# CONNECTORS.net
KiCad netlist of a schematic drawn in Altium Designer
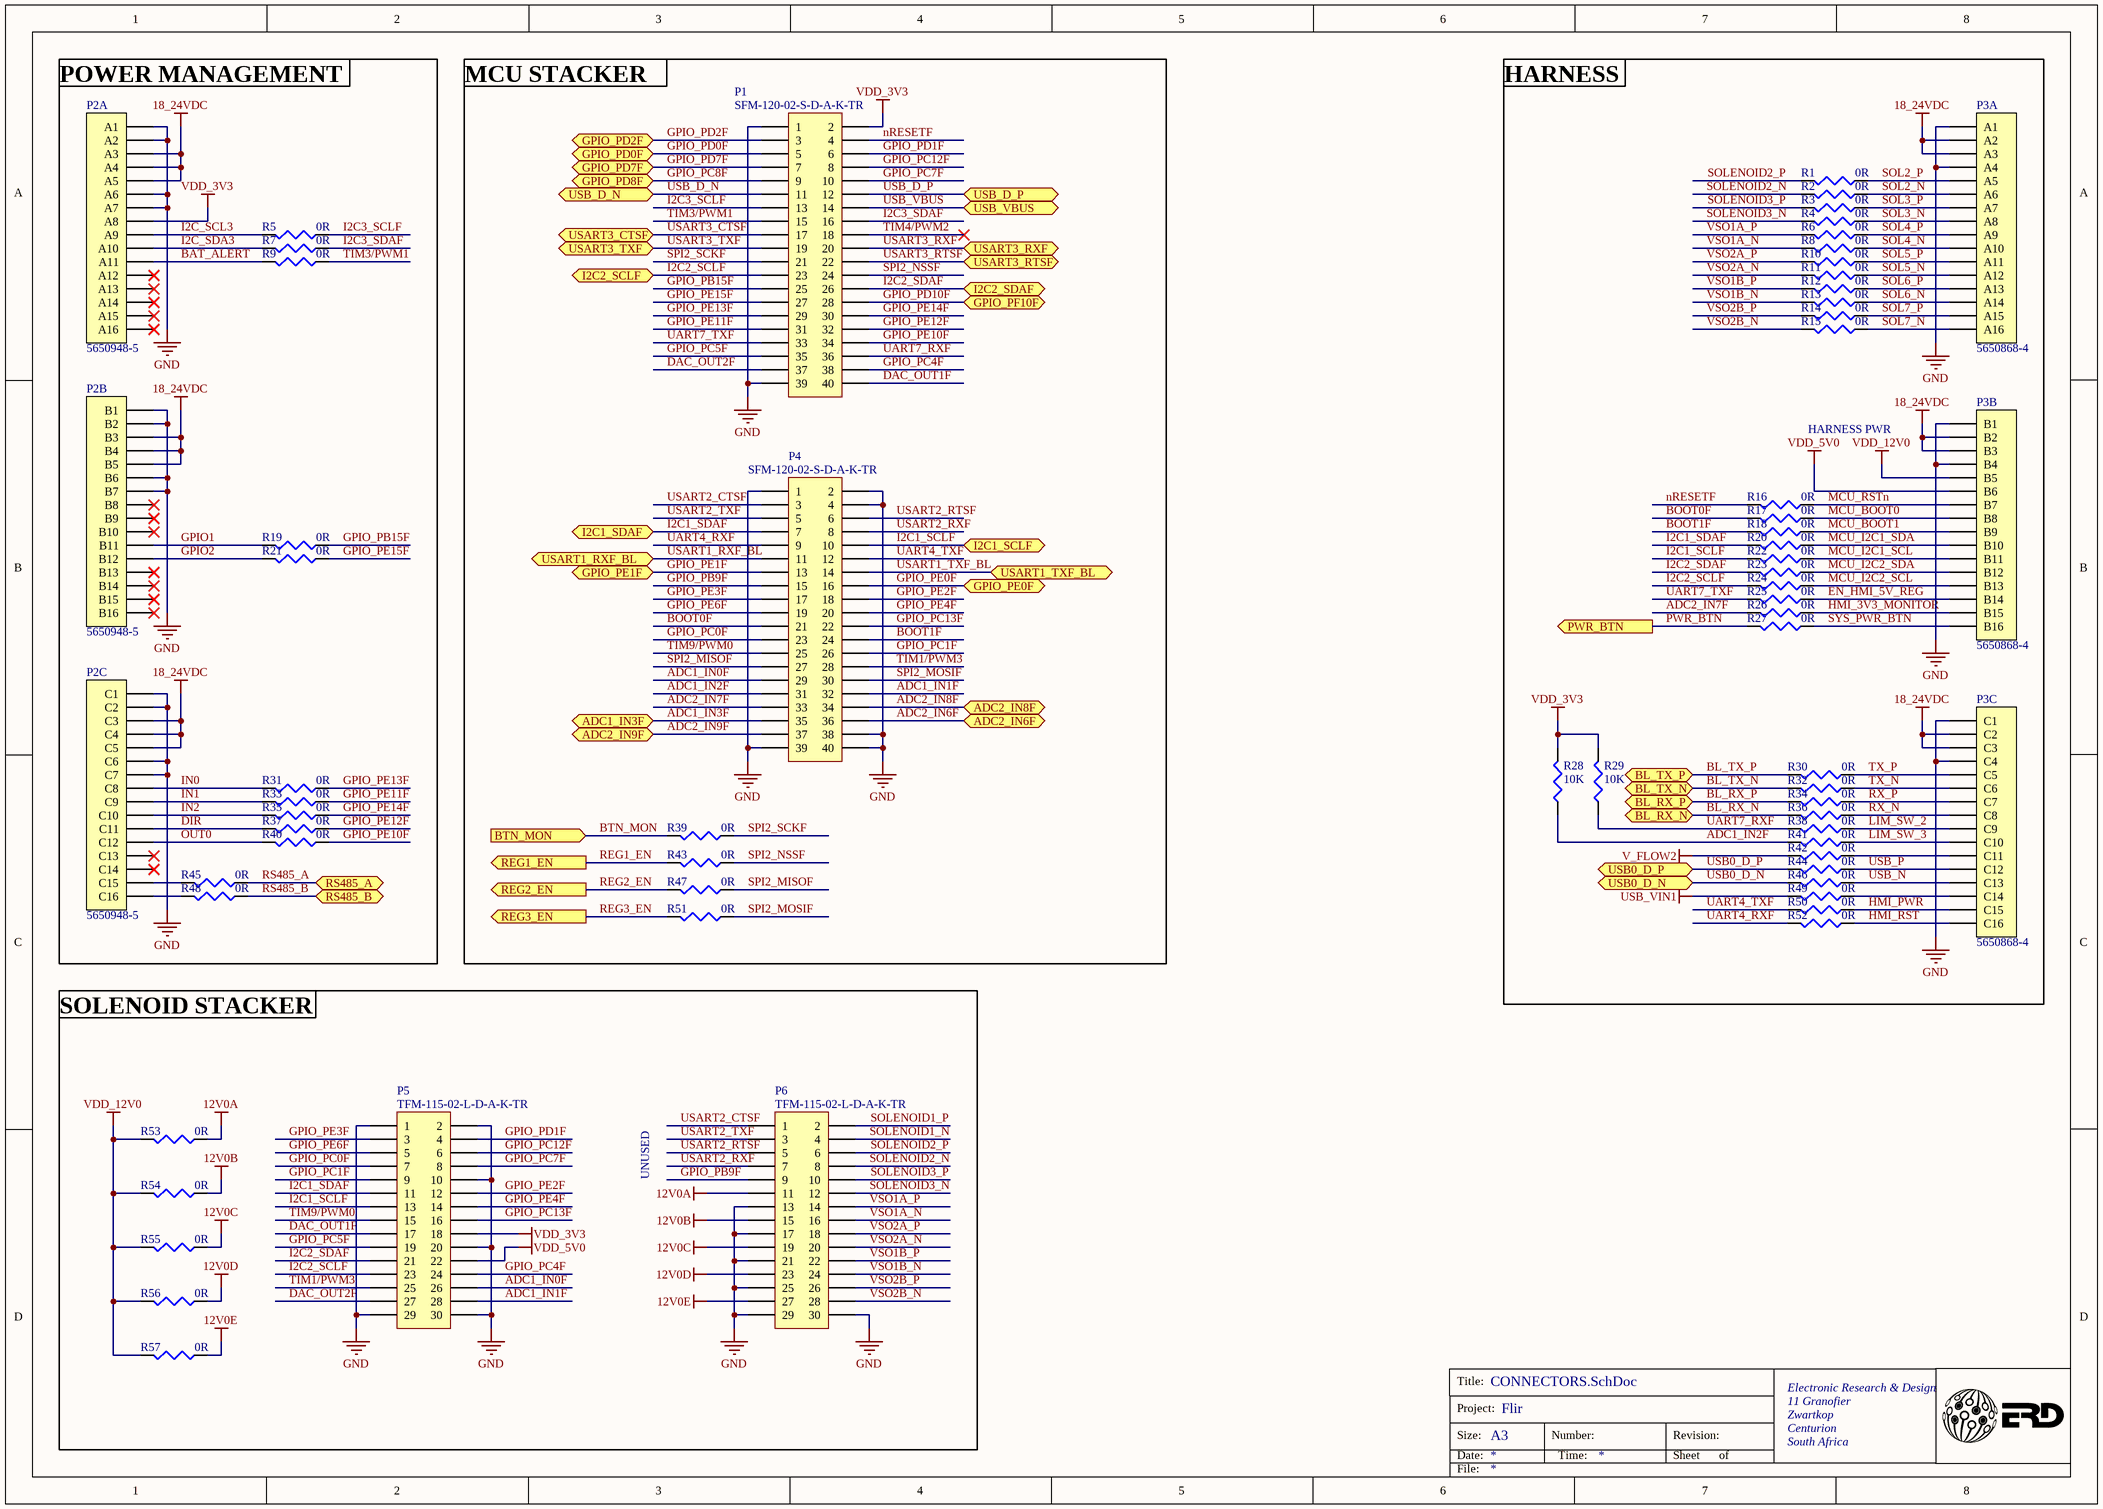
[diagram p0: CONNECTORS.SchDoc]

(export (version "E")
  (design (tool "Eeschema 10.0.6"))
  (components
    (comp (ref "P1")
      (value "SFM-120-02-S-D-A-K-TR")
      (footprint "ERD TiAm:SFM-120-02-S-D-A-K-TR")
      (description "Receptacle, 40 POS, 1.27mm PITCH, SMD")
      (libsource (lib "Miscellaneous Connectors") (part "Header 20X2"))
    )
    (comp (ref "P2")
      (value "5650948-5")
      (footprint "5650948-5_M_RA")
      (description "DIN-41612, C/2, 48-circuit, 3x16, 2.54mm pitch, RA, TH")
      (fields (field (name "MANUFACTURER") "TE Connectivity"))
      (libsource (lib "ERD TiAm") (part "DIN_41612_3x16"))
    )
    (comp (ref "P3")
      (value "5650868-4")
      (footprint "5650868-4_F_RA")
      (description "DIN-41612, R/2, 48-circuit, 3x16, 2.54mm pitch, RA, TH")
      (fields (field (name "MANUFACTURER") "TE Connectivity"))
      (libsource (lib "") (part "DIN_41612_3x16_1"))
    )
    (comp (ref "P4")
      (value "SFM-120-02-S-D-A-K-TR")
      (footprint "ERD TiAm:SFM-120-02-S-D-A-K-TR")
      (description "Receptacle, 40 POS, 1.27mm PITCH, SMD")
      (libsource (lib "Miscellaneous Connectors") (part "Header 20X2"))
    )
    (comp (ref "P5")
      (value "TFM-115-02-L-D-A-K-TR")
      (footprint "ERD TiAm:SFM-115-02-L-D-A-K-TR")
      (description "Header, 30 POS, 1.27mm PITCH, SMD")
      (libsource (lib "Miscellaneous Connectors") (part "Header 15X2"))
    )
    (comp (ref "P6")
      (value "TFM-115-02-L-D-A-K-TR")
      (footprint "ERD TiAm:SFM-115-02-L-D-A-K-TR")
      (description "Header, 30 POS, 1.27mm PITCH, SMD")
      (libsource (lib "Miscellaneous Connectors") (part "Header 15X2"))
    )
    (comp (ref "R1")
      (value "0R")
      (footprint "RC0402")
      (description "RES, 0 OHM, 1/16W, 1%, 0402")
      (fields (field (name "MANUFACTURER") "Yageo") (field (name "PARTNUMBER") "RC0402FR-070RL"))
      (libsource (lib "ERD TiAm") (part "RES_10K_1/16W_1%_0402"))
    )
    (comp (ref "R2")
      (value "0R")
      (footprint "RC0402")
      (description "RES, 0 OHM, 1/16W, 1%, 0402")
      (fields (field (name "MANUFACTURER") "Yageo") (field (name "PARTNUMBER") "RC0402FR-070RL"))
      (libsource (lib "ERD TiAm") (part "RES_10K_1/16W_1%_0402"))
    )
    (comp (ref "R3")
      (value "0R")
      (footprint "RC0402")
      (description "RES, 0 OHM, 1/16W, 1%, 0402")
      (fields (field (name "MANUFACTURER") "Yageo") (field (name "PARTNUMBER") "RC0402FR-070RL"))
      (libsource (lib "ERD TiAm") (part "RES_10K_1/16W_1%_0402"))
    )
    (comp (ref "R4")
      (value "0R")
      (footprint "RC0402")
      (description "RES, 0 OHM, 1/16W, 1%, 0402")
      (fields (field (name "MANUFACTURER") "Yageo") (field (name "PARTNUMBER") "RC0402FR-070RL"))
      (libsource (lib "ERD TiAm") (part "RES_10K_1/16W_1%_0402"))
    )
    (comp (ref "R5")
      (value "0R")
      (footprint "RC0402")
      (description "RES, 0 OHM, 1/16W, 1%, 0402")
      (fields (field (name "MANUFACTURER") "Yageo") (field (name "PARTNUMBER") "RC0402FR-070RL"))
      (libsource (lib "ERD TiAm") (part "RES_10K_1/16W_1%_0402"))
    )
    (comp (ref "R6")
      (value "0R")
      (footprint "RC0402")
      (description "RES, 0 OHM, 1/16W, 1%, 0402")
      (fields (field (name "MANUFACTURER") "Yageo") (field (name "PARTNUMBER") "RC0402FR-070RL"))
      (libsource (lib "ERD TiAm") (part "RES_10K_1/16W_1%_0402"))
    )
    (comp (ref "R7")
      (value "0R")
      (footprint "RC0402")
      (description "RES, 0 OHM, 1/16W, 1%, 0402")
      (fields (field (name "MANUFACTURER") "Yageo") (field (name "PARTNUMBER") "RC0402FR-070RL"))
      (libsource (lib "ERD TiAm") (part "RES_10K_1/16W_1%_0402"))
    )
    (comp (ref "R8")
      (value "0R")
      (footprint "RC0402")
      (description "RES, 0 OHM, 1/16W, 1%, 0402")
      (fields (field (name "MANUFACTURER") "Yageo") (field (name "PARTNUMBER") "RC0402FR-070RL"))
      (libsource (lib "ERD TiAm") (part "RES_10K_1/16W_1%_0402"))
    )
    (comp (ref "R9")
      (value "0R")
      (footprint "RC0402")
      (description "RES, 0 OHM, 1/16W, 1%, 0402")
      (fields (field (name "MANUFACTURER") "Yageo") (field (name "PARTNUMBER") "RC0402FR-070RL"))
      (libsource (lib "ERD TiAm") (part "RES_10K_1/16W_1%_0402"))
    )
    (comp (ref "R10")
      (value "0R")
      (footprint "RC0402")
      (description "RES, 0 OHM, 1/16W, 1%, 0402")
      (fields (field (name "MANUFACTURER") "Yageo") (field (name "PARTNUMBER") "RC0402FR-070RL"))
      (libsource (lib "ERD TiAm") (part "RES_10K_1/16W_1%_0402"))
    )
    (comp (ref "R11")
      (value "0R")
      (footprint "RC0402")
      (description "RES, 0 OHM, 1/16W, 1%, 0402")
      (fields (field (name "MANUFACTURER") "Yageo") (field (name "PARTNUMBER") "RC0402FR-070RL"))
      (libsource (lib "ERD TiAm") (part "RES_10K_1/16W_1%_0402"))
    )
    (comp (ref "R12")
      (value "0R")
      (footprint "RC0402")
      (description "RES, 0 OHM, 1/16W, 1%, 0402")
      (fields (field (name "MANUFACTURER") "Yageo") (field (name "PARTNUMBER") "RC0402FR-070RL"))
      (libsource (lib "ERD TiAm") (part "RES_10K_1/16W_1%_0402"))
    )
    (comp (ref "R13")
      (value "0R")
      (footprint "RC0402")
      (description "RES, 0 OHM, 1/16W, 1%, 0402")
      (fields (field (name "MANUFACTURER") "Yageo") (field (name "PARTNUMBER") "RC0402FR-070RL"))
      (libsource (lib "ERD TiAm") (part "RES_10K_1/16W_1%_0402"))
    )
    (comp (ref "R14")
      (value "0R")
      (footprint "RC0402")
      (description "RES, 0 OHM, 1/16W, 1%, 0402")
      (fields (field (name "MANUFACTURER") "Yageo") (field (name "PARTNUMBER") "RC0402FR-070RL"))
      (libsource (lib "ERD TiAm") (part "RES_10K_1/16W_1%_0402"))
    )
    (comp (ref "R15")
      (value "0R")
      (footprint "RC0402")
      (description "RES, 0 OHM, 1/16W, 1%, 0402")
      (fields (field (name "MANUFACTURER") "Yageo") (field (name "PARTNUMBER") "RC0402FR-070RL"))
      (libsource (lib "ERD TiAm") (part "RES_10K_1/16W_1%_0402"))
    )
    (comp (ref "R16")
      (value "0R")
      (footprint "RC0402")
      (description "RES, 0 OHM, 1/16W, 1%, 0402")
      (fields (field (name "MANUFACTURER") "Yageo") (field (name "PARTNUMBER") "RC0402FR-070RL"))
      (libsource (lib "ERD TiAm") (part "RES_10K_1/16W_1%_0402"))
    )
    (comp (ref "R17")
      (value "0R")
      (footprint "RC0402")
      (description "RES, 0 OHM, 1/16W, 1%, 0402")
      (fields (field (name "MANUFACTURER") "Yageo") (field (name "PARTNUMBER") "RC0402FR-070RL"))
      (libsource (lib "ERD TiAm") (part "RES_10K_1/16W_1%_0402"))
    )
    (comp (ref "R18")
      (value "0R")
      (footprint "RC0402")
      (description "RES, 0 OHM, 1/16W, 1%, 0402")
      (fields (field (name "MANUFACTURER") "Yageo") (field (name "PARTNUMBER") "RC0402FR-070RL"))
      (libsource (lib "ERD TiAm") (part "RES_10K_1/16W_1%_0402"))
    )
    (comp (ref "R19")
      (value "0R")
      (footprint "RC0402")
      (description "RES, 0 OHM, 1/16W, 1%, 0402")
      (fields (field (name "MANUFACTURER") "Yageo") (field (name "PARTNUMBER") "RC0402FR-070RL"))
      (libsource (lib "ERD TiAm") (part "RES_10K_1/16W_1%_0402"))
    )
    (comp (ref "R20")
      (value "0R")
      (footprint "RC0402")
      (description "RES, 0 OHM, 1/16W, 1%, 0402")
      (fields (field (name "MANUFACTURER") "Yageo") (field (name "PARTNUMBER") "RC0402FR-070RL"))
      (libsource (lib "ERD TiAm") (part "RES_10K_1/16W_1%_0402"))
    )
    (comp (ref "R21")
      (value "0R")
      (footprint "RC0402")
      (description "RES, 0 OHM, 1/16W, 1%, 0402")
      (fields (field (name "MANUFACTURER") "Yageo") (field (name "PARTNUMBER") "RC0402FR-070RL"))
      (libsource (lib "ERD TiAm") (part "RES_10K_1/16W_1%_0402"))
    )
    (comp (ref "R22")
      (value "0R")
      (footprint "RC0402")
      (description "RES, 0 OHM, 1/16W, 1%, 0402")
      (fields (field (name "MANUFACTURER") "Yageo") (field (name "PARTNUMBER") "RC0402FR-070RL"))
      (libsource (lib "ERD TiAm") (part "RES_10K_1/16W_1%_0402"))
    )
    (comp (ref "R23")
      (value "0R")
      (footprint "RC0402")
      (description "RES, 0 OHM, 1/16W, 1%, 0402")
      (fields (field (name "MANUFACTURER") "Yageo") (field (name "PARTNUMBER") "RC0402FR-070RL"))
      (libsource (lib "ERD TiAm") (part "RES_10K_1/16W_1%_0402"))
    )
    (comp (ref "R24")
      (value "0R")
      (footprint "RC0402")
      (description "RES, 0 OHM, 1/16W, 1%, 0402")
      (fields (field (name "MANUFACTURER") "Yageo") (field (name "PARTNUMBER") "RC0402FR-070RL"))
      (libsource (lib "ERD TiAm") (part "RES_10K_1/16W_1%_0402"))
    )
    (comp (ref "R25")
      (value "0R")
      (footprint "RC0402")
      (description "RES, 0 OHM, 1/16W, 1%, 0402")
      (fields (field (name "MANUFACTURER") "Yageo") (field (name "PARTNUMBER") "RC0402FR-070RL"))
      (libsource (lib "ERD TiAm") (part "RES_10K_1/16W_1%_0402"))
    )
    (comp (ref "R26")
      (value "0R")
      (footprint "RC0402")
      (description "RES, 0 OHM, 1/16W, 1%, 0402")
      (fields (field (name "MANUFACTURER") "Yageo") (field (name "PARTNUMBER") "RC0402FR-070RL"))
      (libsource (lib "ERD TiAm") (part "RES_10K_1/16W_1%_0402"))
    )
    (comp (ref "R27")
      (value "0R")
      (footprint "RC0402")
      (description "RES, 0 OHM, 1/16W, 1%, 0402")
      (fields (field (name "MANUFACTURER") "Yageo") (field (name "PARTNUMBER") "RC0402FR-070RL"))
      (libsource (lib "ERD TiAm") (part "RES_10K_1/16W_1%_0402"))
    )
    (comp (ref "R28")
      (value "10K")
      (footprint "RC0402")
      (description "RES, 10K OHM, 1/16W, 1%, 0402")
      (fields (field (name "MANUFACTURER") "Yageo") (field (name "PART NUMBER") "RC0402FR-0710KL"))
      (libsource (lib "ERD TiAm") (part "RES_10K_1/16W_1%_0402"))
    )
    (comp (ref "R29")
      (value "10K")
      (footprint "RC0402")
      (description "RES, 10K OHM, 1/16W, 1%, 0402")
      (fields (field (name "MANUFACTURER") "Yageo") (field (name "PART NUMBER") "RC0402FR-0710KL"))
      (libsource (lib "ERD TiAm") (part "RES_10K_1/16W_1%_0402"))
    )
    (comp (ref "R30")
      (value "0R")
      (footprint "RC0402")
      (description "RES, 0 OHM, 1/16W, 1%, 0402")
      (fields (field (name "MANUFACTURER") "Yageo") (field (name "PARTNUMBER") "RC0402FR-070RL"))
      (libsource (lib "ERD TiAm") (part "RES_10K_1/16W_1%_0402"))
    )
    (comp (ref "R31")
      (value "0R")
      (footprint "RC0402")
      (description "RES, 0 OHM, 1/16W, 1%, 0402")
      (fields (field (name "MANUFACTURER") "Yageo") (field (name "PARTNUMBER") "RC0402FR-070RL"))
      (libsource (lib "ERD TiAm") (part "RES_10K_1/16W_1%_0402"))
    )
    (comp (ref "R32")
      (value "0R")
      (footprint "RC0402")
      (description "RES, 0 OHM, 1/16W, 1%, 0402")
      (fields (field (name "MANUFACTURER") "Yageo") (field (name "PARTNUMBER") "RC0402FR-070RL"))
      (libsource (lib "ERD TiAm") (part "RES_10K_1/16W_1%_0402"))
    )
    (comp (ref "R33")
      (value "0R")
      (footprint "RC0402")
      (description "RES, 0 OHM, 1/16W, 1%, 0402")
      (fields (field (name "MANUFACTURER") "Yageo") (field (name "PARTNUMBER") "RC0402FR-070RL"))
      (libsource (lib "ERD TiAm") (part "RES_10K_1/16W_1%_0402"))
    )
    (comp (ref "R34")
      (value "0R")
      (footprint "RC0402")
      (description "RES, 0 OHM, 1/16W, 1%, 0402")
      (fields (field (name "MANUFACTURER") "Yageo") (field (name "PARTNUMBER") "RC0402FR-070RL"))
      (libsource (lib "ERD TiAm") (part "RES_10K_1/16W_1%_0402"))
    )
    (comp (ref "R35")
      (value "0R")
      (footprint "RC0402")
      (description "RES, 0 OHM, 1/16W, 1%, 0402")
      (fields (field (name "MANUFACTURER") "Yageo") (field (name "PARTNUMBER") "RC0402FR-070RL"))
      (libsource (lib "ERD TiAm") (part "RES_10K_1/16W_1%_0402"))
    )
    (comp (ref "R36")
      (value "0R")
      (footprint "RC0402")
      (description "RES, 0 OHM, 1/16W, 1%, 0402")
      (fields (field (name "MANUFACTURER") "Yageo") (field (name "PARTNUMBER") "RC0402FR-070RL"))
      (libsource (lib "ERD TiAm") (part "RES_10K_1/16W_1%_0402"))
    )
    (comp (ref "R37")
      (value "0R")
      (footprint "RC0402")
      (description "RES, 0 OHM, 1/16W, 1%, 0402")
      (fields (field (name "MANUFACTURER") "Yageo") (field (name "PARTNUMBER") "RC0402FR-070RL"))
      (libsource (lib "ERD TiAm") (part "RES_10K_1/16W_1%_0402"))
    )
    (comp (ref "R38")
      (value "0R")
      (footprint "RC0402")
      (description "RES, 0 OHM, 1/16W, 1%, 0402")
      (fields (field (name "MANUFACTURER") "Yageo") (field (name "PARTNUMBER") "RC0402FR-070RL"))
      (libsource (lib "ERD TiAm") (part "RES_10K_1/16W_1%_0402"))
    )
    (comp (ref "R39")
      (value "0R")
      (footprint "RC0402")
      (description "RES, 0 OHM, 1/16W, 1%, 0402")
      (fields (field (name "MANUFACTURER") "Yageo") (field (name "PARTNUMBER") "RC0402FR-070RL"))
      (libsource (lib "ERD TiAm") (part "RES_10K_1/16W_1%_0402"))
    )
    (comp (ref "R40")
      (value "0R")
      (footprint "RC0402")
      (description "RES, 0 OHM, 1/16W, 1%, 0402")
      (fields (field (name "MANUFACTURER") "Yageo") (field (name "PARTNUMBER") "RC0402FR-070RL"))
      (libsource (lib "ERD TiAm") (part "RES_10K_1/16W_1%_0402"))
    )
    (comp (ref "R41")
      (value "0R")
      (footprint "RC0402")
      (description "RES, 0 OHM, 1/16W, 1%, 0402")
      (fields (field (name "MANUFACTURER") "Yageo") (field (name "PARTNUMBER") "RC0402FR-070RL"))
      (libsource (lib "ERD TiAm") (part "RES_10K_1/16W_1%_0402"))
    )
    (comp (ref "R42")
      (value "0R")
      (footprint "RC0402")
      (description "RES, 0 OHM, 1/16W, 1%, 0402")
      (fields (field (name "MANUFACTURER") "Yageo") (field (name "PARTNUMBER") "RC0402FR-070RL"))
      (libsource (lib "ERD TiAm") (part "RES_10K_1/16W_1%_0402"))
    )
    (comp (ref "R43")
      (value "0R")
      (footprint "RC0402")
      (description "RES, 0 OHM, 1/16W, 1%, 0402")
      (fields (field (name "MANUFACTURER") "Yageo") (field (name "PARTNUMBER") "RC0402FR-070RL"))
      (libsource (lib "ERD TiAm") (part "RES_10K_1/16W_1%_0402"))
    )
    (comp (ref "R44")
      (value "0R")
      (footprint "RC0402")
      (description "RES, 0 OHM, 1/16W, 1%, 0402")
      (fields (field (name "MANUFACTURER") "Yageo") (field (name "PARTNUMBER") "RC0402FR-070RL"))
      (libsource (lib "ERD TiAm") (part "RES_10K_1/16W_1%_0402"))
    )
    (comp (ref "R45")
      (value "0R")
      (footprint "RC0402")
      (description "RES, 0 OHM, 1/16W, 1%, 0402")
      (fields (field (name "MANUFACTURER") "Yageo") (field (name "PARTNUMBER") "RC0402FR-070RL"))
      (libsource (lib "ERD TiAm") (part "RES_10K_1/16W_1%_0402"))
    )
    (comp (ref "R46")
      (value "0R")
      (footprint "RC0402")
      (description "RES, 0 OHM, 1/16W, 1%, 0402")
      (fields (field (name "MANUFACTURER") "Yageo") (field (name "PARTNUMBER") "RC0402FR-070RL"))
      (libsource (lib "ERD TiAm") (part "RES_10K_1/16W_1%_0402"))
    )
    (comp (ref "R47")
      (value "0R")
      (footprint "RC0402")
      (description "RES, 0 OHM, 1/16W, 1%, 0402")
      (fields (field (name "MANUFACTURER") "Yageo") (field (name "PARTNUMBER") "RC0402FR-070RL"))
      (libsource (lib "ERD TiAm") (part "RES_10K_1/16W_1%_0402"))
    )
    (comp (ref "R48")
      (value "0R")
      (footprint "RC0402")
      (description "RES, 0 OHM, 1/16W, 1%, 0402")
      (fields (field (name "MANUFACTURER") "Yageo") (field (name "PARTNUMBER") "RC0402FR-070RL"))
      (libsource (lib "ERD TiAm") (part "RES_10K_1/16W_1%_0402"))
    )
    (comp (ref "R49")
      (value "0R")
      (footprint "RC0402")
      (description "RES, 0 OHM, 1/16W, 1%, 0402")
      (fields (field (name "MANUFACTURER") "Yageo") (field (name "PARTNUMBER") "RC0402FR-070RL"))
      (libsource (lib "ERD TiAm") (part "RES_10K_1/16W_1%_0402"))
    )
    (comp (ref "R50")
      (value "0R")
      (footprint "RC0402")
      (description "RES, 0 OHM, 1/16W, 1%, 0402")
      (fields (field (name "MANUFACTURER") "Yageo") (field (name "PARTNUMBER") "RC0402FR-070RL"))
      (libsource (lib "ERD TiAm") (part "RES_10K_1/16W_1%_0402"))
    )
    (comp (ref "R51")
      (value "0R")
      (footprint "RC0402")
      (description "RES, 0 OHM, 1/16W, 1%, 0402")
      (fields (field (name "MANUFACTURER") "Yageo") (field (name "PARTNUMBER") "RC0402FR-070RL"))
      (libsource (lib "ERD TiAm") (part "RES_10K_1/16W_1%_0402"))
    )
    (comp (ref "R52")
      (value "0R")
      (footprint "RC0402")
      (description "RES, 0 OHM, 1/16W, 1%, 0402")
      (fields (field (name "MANUFACTURER") "Yageo") (field (name "PARTNUMBER") "RC0402FR-070RL"))
      (libsource (lib "ERD TiAm") (part "RES_10K_1/16W_1%_0402"))
    )
    (comp (ref "R53")
      (value "0R")
      (footprint "RC0603")
      (description "RES, 0 OHM, 1/10W, 50mOhm (5%), 0603")
      (fields (field (name "MANUFACTURER") "Yageo") (field (name "PARTNUMBER") "RC0603JR-070RP"))
      (libsource (lib "ERD TiAm") (part "RES_10K_1/16W_1%_0402"))
    )
    (comp (ref "R54")
      (value "0R")
      (footprint "RC0603")
      (description "RES, 0 OHM, 1/10W, 50mOhm (5%), 0603")
      (fields (field (name "MANUFACTURER") "Yageo") (field (name "PARTNUMBER") "RC0603JR-070RP"))
      (libsource (lib "ERD TiAm") (part "RES_10K_1/16W_1%_0402"))
    )
    (comp (ref "R55")
      (value "0R")
      (footprint "RC0603")
      (description "RES, 0 OHM, 1/10W, 50mOhm (5%), 0603")
      (fields (field (name "MANUFACTURER") "Yageo") (field (name "PARTNUMBER") "RC0603JR-070RP"))
      (libsource (lib "ERD TiAm") (part "RES_10K_1/16W_1%_0402"))
    )
    (comp (ref "R56")
      (value "0R")
      (footprint "RC0603")
      (description "RES, 0 OHM, 1/10W, 50mOhm (5%), 0603")
      (fields (field (name "MANUFACTURER") "Yageo") (field (name "PARTNUMBER") "RC0603JR-070RP"))
      (libsource (lib "ERD TiAm") (part "RES_10K_1/16W_1%_0402"))
    )
    (comp (ref "R57")
      (value "0R")
      (footprint "RC0603")
      (description "RES, 0 OHM, 1/10W, 50mOhm (5%), 0603")
      (fields (field (name "MANUFACTURER") "Yageo") (field (name "PARTNUMBER") "RC0603JR-070RP"))
      (libsource (lib "ERD TiAm") (part "RES_10K_1/16W_1%_0402"))
    )
  )
  (nets
    (net (code "1") (name "/ADC1_IN0F") (class "Default")
      (node (ref "P4") (pin "29") (pinfunction "29_29") (pintype "passive"))
      (node (ref "P5") (pin "26") (pinfunction "26_26") (pintype "passive"))
    )
    (net (code "2") (name "/ADC1_IN1F") (class "Default")
      (node (ref "P4") (pin "32") (pinfunction "32_32") (pintype "passive"))
      (node (ref "P5") (pin "28") (pinfunction "28_28") (pintype "passive"))
    )
    (net (code "3") (name "/ADC1_IN2F") (class "Default")
      (node (ref "P4") (pin "31") (pinfunction "31_31") (pintype "passive"))
      (node (ref "R28") (pin "1") (pinfunction "1_1") (pintype "passive"))
      (node (ref "R41") (pin "2") (pinfunction "2_2") (pintype "passive"))
    )
    (net (code "4") (name "/ADC1_IN3F") (class "Default")
      (node (ref "P4") (pin "35") (pinfunction "35_35") (pintype "passive"))
    )
    (net (code "5") (name "/ADC2_IN6F") (class "Default")
      (node (ref "P4") (pin "36") (pinfunction "36_36") (pintype "passive"))
    )
    (net (code "6") (name "/ADC2_IN7F") (class "Default")
      (node (ref "P4") (pin "33") (pinfunction "33_33") (pintype "passive"))
      (node (ref "R26") (pin "2") (pinfunction "2_2") (pintype "passive"))
    )
    (net (code "7") (name "/ADC2_IN8F") (class "Default")
      (node (ref "P4") (pin "34") (pinfunction "34_34") (pintype "passive"))
    )
    (net (code "8") (name "/ADC2_IN9F") (class "Default")
      (node (ref "P4") (pin "37") (pinfunction "37_37") (pintype "passive"))
    )
    (net (code "9") (name "/BAT_ALERT") (class "Default")
      (node (ref "P2") (pin "11") (pinfunction "A11_11") (pintype "passive"))
      (node (ref "R9") (pin "2") (pinfunction "2_2") (pintype "passive"))
    )
    (net (code "10") (name "/BL_RX_N") (class "Default")
      (node (ref "R36") (pin "2") (pinfunction "2_2") (pintype "passive"))
    )
    (net (code "11") (name "/BL_RX_P") (class "Default")
      (node (ref "R34") (pin "2") (pinfunction "2_2") (pintype "passive"))
    )
    (net (code "12") (name "/BL_TX_N") (class "Default")
      (node (ref "R32") (pin "2") (pinfunction "2_2") (pintype "passive"))
    )
    (net (code "13") (name "/BL_TX_P") (class "Default")
      (node (ref "R30") (pin "2") (pinfunction "2_2") (pintype "passive"))
    )
    (net (code "14") (name "/BOOT0F") (class "Default")
      (node (ref "P4") (pin "21") (pinfunction "21_21") (pintype "passive"))
      (node (ref "R17") (pin "2") (pinfunction "2_2") (pintype "passive"))
    )
    (net (code "15") (name "/BOOT1F") (class "Default")
      (node (ref "P4") (pin "24") (pinfunction "24_24") (pintype "passive"))
      (node (ref "R18") (pin "2") (pinfunction "2_2") (pintype "passive"))
    )
    (net (code "16") (name "/BTN_MON") (class "Default")
      (node (ref "R39") (pin "2") (pinfunction "2_2") (pintype "passive"))
    )
    (net (code "17") (name "/DAC_OUT1F") (class "Default")
      (node (ref "P1") (pin "40") (pinfunction "40_40") (pintype "passive"))
      (node (ref "P5") (pin "17") (pinfunction "17_17") (pintype "passive"))
    )
    (net (code "18") (name "/DAC_OUT2F") (class "Default")
      (node (ref "P1") (pin "37") (pinfunction "37_37") (pintype "passive"))
      (node (ref "P5") (pin "27") (pinfunction "27_27") (pintype "passive"))
    )
    (net (code "19") (name "/DIR") (class "Default")
      (node (ref "P2") (pin "43") (pinfunction "C11_43") (pintype "passive"))
      (node (ref "R37") (pin "2") (pinfunction "2_2") (pintype "passive"))
    )
    (net (code "20") (name "/EN_HMI_5V_REG") (class "Default")
      (node (ref "P3") (pin "30") (pinfunction "B14_30") (pintype "passive"))
      (node (ref "R25") (pin "1") (pinfunction "1_1") (pintype "passive"))
    )
    (net (code "21") (name "/GPIO1") (class "Default")
      (node (ref "P2") (pin "27") (pinfunction "B11_27") (pintype "passive"))
      (node (ref "R19") (pin "2") (pinfunction "2_2") (pintype "passive"))
    )
    (net (code "22") (name "/GPIO2") (class "Default")
      (node (ref "P2") (pin "28") (pinfunction "B12_28") (pintype "passive"))
      (node (ref "R21") (pin "2") (pinfunction "2_2") (pintype "passive"))
    )
    (net (code "23") (name "/GPIO_PB9F") (class "Default")
      (node (ref "P4") (pin "15") (pinfunction "15_15") (pintype "passive"))
      (node (ref "P6") (pin "9") (pinfunction "9_9") (pintype "passive"))
    )
    (net (code "24") (name "/GPIO_PB15F") (class "Default")
      (node (ref "P1") (pin "25") (pinfunction "25_25") (pintype "passive"))
      (node (ref "R19") (pin "1") (pinfunction "1_1") (pintype "passive"))
    )
    (net (code "25") (name "/GPIO_PC0F") (class "Default")
      (node (ref "P4") (pin "23") (pinfunction "23_23") (pintype "passive"))
      (node (ref "P5") (pin "7") (pinfunction "7_7") (pintype "passive"))
    )
    (net (code "26") (name "/GPIO_PC1F") (class "Default")
      (node (ref "P4") (pin "26") (pinfunction "26_26") (pintype "passive"))
      (node (ref "P5") (pin "9") (pinfunction "9_9") (pintype "passive"))
    )
    (net (code "27") (name "/GPIO_PC4F") (class "Default")
      (node (ref "P1") (pin "38") (pinfunction "38_38") (pintype "passive"))
      (node (ref "P5") (pin "24") (pinfunction "24_24") (pintype "passive"))
    )
    (net (code "28") (name "/GPIO_PC5F") (class "Default")
      (node (ref "P1") (pin "35") (pinfunction "35_35") (pintype "passive"))
      (node (ref "P5") (pin "19") (pinfunction "19_19") (pintype "passive"))
    )
    (net (code "29") (name "/GPIO_PC7F") (class "Default")
      (node (ref "P1") (pin "10") (pinfunction "10_10") (pintype "passive"))
      (node (ref "P5") (pin "8") (pinfunction "8_8") (pintype "passive"))
    )
    (net (code "30") (name "/GPIO_PC8F") (class "Default")
      (node (ref "P1") (pin "9") (pinfunction "9_9") (pintype "passive"))
    )
    (net (code "31") (name "/GPIO_PC12F") (class "Default")
      (node (ref "P1") (pin "8") (pinfunction "8_8") (pintype "passive"))
      (node (ref "P5") (pin "6") (pinfunction "6_6") (pintype "passive"))
    )
    (net (code "32") (name "/GPIO_PC13F") (class "Default")
      (node (ref "P4") (pin "22") (pinfunction "22_22") (pintype "passive"))
      (node (ref "P5") (pin "16") (pinfunction "16_16") (pintype "passive"))
    )
    (net (code "33") (name "/GPIO_PD0F") (class "Default")
      (node (ref "P1") (pin "5") (pinfunction "5_5") (pintype "passive"))
    )
    (net (code "34") (name "/GPIO_PD1F") (class "Default")
      (node (ref "P1") (pin "6") (pinfunction "6_6") (pintype "passive"))
      (node (ref "P5") (pin "4") (pinfunction "4_4") (pintype "passive"))
    )
    (net (code "35") (name "/GPIO_PD2F") (class "Default")
      (node (ref "P1") (pin "3") (pinfunction "3_3") (pintype "passive"))
    )
    (net (code "36") (name "/GPIO_PD7F") (class "Default")
      (node (ref "P1") (pin "7") (pinfunction "7_7") (pintype "passive"))
    )
    (net (code "37") (name "/GPIO_PD10F") (class "Default")
      (node (ref "P1") (pin "28") (pinfunction "28_28") (pintype "passive"))
    )
    (net (code "38") (name "/GPIO_PE0F") (class "Default")
      (node (ref "P4") (pin "16") (pinfunction "16_16") (pintype "passive"))
    )
    (net (code "39") (name "/GPIO_PE1F") (class "Default")
      (node (ref "P4") (pin "13") (pinfunction "13_13") (pintype "passive"))
    )
    (net (code "40") (name "/GPIO_PE2F") (class "Default")
      (node (ref "P4") (pin "18") (pinfunction "18_18") (pintype "passive"))
      (node (ref "P5") (pin "12") (pinfunction "12_12") (pintype "passive"))
    )
    (net (code "41") (name "/GPIO_PE3F") (class "Default")
      (node (ref "P4") (pin "17") (pinfunction "17_17") (pintype "passive"))
      (node (ref "P5") (pin "3") (pinfunction "3_3") (pintype "passive"))
    )
    (net (code "42") (name "/GPIO_PE4F") (class "Default")
      (node (ref "P4") (pin "20") (pinfunction "20_20") (pintype "passive"))
      (node (ref "P5") (pin "14") (pinfunction "14_14") (pintype "passive"))
    )
    (net (code "43") (name "/GPIO_PE6F") (class "Default")
      (node (ref "P4") (pin "19") (pinfunction "19_19") (pintype "passive"))
      (node (ref "P5") (pin "5") (pinfunction "5_5") (pintype "passive"))
    )
    (net (code "44") (name "/GPIO_PE10F") (class "Default")
      (node (ref "P1") (pin "34") (pinfunction "34_34") (pintype "passive"))
      (node (ref "R40") (pin "1") (pinfunction "1_1") (pintype "passive"))
    )
    (net (code "45") (name "/GPIO_PE11F") (class "Default")
      (node (ref "P1") (pin "31") (pinfunction "31_31") (pintype "passive"))
      (node (ref "R33") (pin "1") (pinfunction "1_1") (pintype "passive"))
    )
    (net (code "46") (name "/GPIO_PE12F") (class "Default")
      (node (ref "P1") (pin "32") (pinfunction "32_32") (pintype "passive"))
      (node (ref "R37") (pin "1") (pinfunction "1_1") (pintype "passive"))
    )
    (net (code "47") (name "/GPIO_PE13F") (class "Default")
      (node (ref "P1") (pin "29") (pinfunction "29_29") (pintype "passive"))
      (node (ref "R31") (pin "1") (pinfunction "1_1") (pintype "passive"))
    )
    (net (code "48") (name "/GPIO_PE14F") (class "Default")
      (node (ref "P1") (pin "30") (pinfunction "30_30") (pintype "passive"))
      (node (ref "R35") (pin "1") (pinfunction "1_1") (pintype "passive"))
    )
    (net (code "49") (name "/GPIO_PE15F") (class "Default")
      (node (ref "P1") (pin "27") (pinfunction "27_27") (pintype "passive"))
      (node (ref "R21") (pin "1") (pinfunction "1_1") (pintype "passive"))
    )
    (net (code "50") (name "/HMI_3V3_MONITOR") (class "Default")
      (node (ref "P3") (pin "31") (pinfunction "B15_31") (pintype "passive"))
      (node (ref "R26") (pin "1") (pinfunction "1_1") (pintype "passive"))
    )
    (net (code "51") (name "/HMI_PWR") (class "Default")
      (node (ref "P3") (pin "47") (pinfunction "C15_47") (pintype "passive"))
      (node (ref "R50") (pin "1") (pinfunction "1_1") (pintype "passive"))
    )
    (net (code "52") (name "/HMI_RST") (class "Default")
      (node (ref "P3") (pin "48") (pinfunction "C16_48") (pintype "passive"))
      (node (ref "R52") (pin "1") (pinfunction "1_1") (pintype "passive"))
    )
    (net (code "53") (name "/I2C1_SCLF") (class "Default")
      (node (ref "P4") (pin "10") (pinfunction "10_10") (pintype "passive"))
      (node (ref "P5") (pin "13") (pinfunction "13_13") (pintype "passive"))
      (node (ref "R22") (pin "2") (pinfunction "2_2") (pintype "passive"))
    )
    (net (code "54") (name "/I2C1_SDAF") (class "Default")
      (node (ref "P4") (pin "7") (pinfunction "7_7") (pintype "passive"))
      (node (ref "P5") (pin "11") (pinfunction "11_11") (pintype "passive"))
      (node (ref "R20") (pin "2") (pinfunction "2_2") (pintype "passive"))
    )
    (net (code "55") (name "/I2C2_SCLF") (class "Default")
      (node (ref "P1") (pin "23") (pinfunction "23_23") (pintype "passive"))
      (node (ref "P5") (pin "23") (pinfunction "23_23") (pintype "passive"))
      (node (ref "R24") (pin "2") (pinfunction "2_2") (pintype "passive"))
    )
    (net (code "56") (name "/I2C2_SDAF") (class "Default")
      (node (ref "P1") (pin "26") (pinfunction "26_26") (pintype "passive"))
      (node (ref "P5") (pin "21") (pinfunction "21_21") (pintype "passive"))
      (node (ref "R23") (pin "2") (pinfunction "2_2") (pintype "passive"))
    )
    (net (code "57") (name "/I2C3_SCLF") (class "Default")
      (node (ref "P1") (pin "13") (pinfunction "13_13") (pintype "passive"))
      (node (ref "R5") (pin "1") (pinfunction "1_1") (pintype "passive"))
    )
    (net (code "58") (name "/I2C3_SDAF") (class "Default")
      (node (ref "P1") (pin "16") (pinfunction "16_16") (pintype "passive"))
      (node (ref "R7") (pin "1") (pinfunction "1_1") (pintype "passive"))
    )
    (net (code "59") (name "/I2C_SCL3") (class "Default")
      (node (ref "P2") (pin "9") (pinfunction "A9_9") (pintype "passive"))
      (node (ref "R5") (pin "2") (pinfunction "2_2") (pintype "passive"))
    )
    (net (code "60") (name "/I2C_SDA3") (class "Default")
      (node (ref "P2") (pin "10") (pinfunction "A10_10") (pintype "passive"))
      (node (ref "R7") (pin "2") (pinfunction "2_2") (pintype "passive"))
    )
    (net (code "61") (name "/IN0") (class "Default")
      (node (ref "P2") (pin "40") (pinfunction "C8_40") (pintype "passive"))
      (node (ref "R31") (pin "2") (pinfunction "2_2") (pintype "passive"))
    )
    (net (code "62") (name "/IN1") (class "Default")
      (node (ref "P2") (pin "41") (pinfunction "C9_41") (pintype "passive"))
      (node (ref "R33") (pin "2") (pinfunction "2_2") (pintype "passive"))
    )
    (net (code "63") (name "/IN2") (class "Default")
      (node (ref "P2") (pin "42") (pinfunction "C10_42") (pintype "passive"))
      (node (ref "R35") (pin "2") (pinfunction "2_2") (pintype "passive"))
    )
    (net (code "64") (name "/LIM_SW_2") (class "Default")
      (node (ref "P3") (pin "41") (pinfunction "C9_41") (pintype "passive"))
      (node (ref "R38") (pin "1") (pinfunction "1_1") (pintype "passive"))
    )
    (net (code "65") (name "/LIM_SW_3") (class "Default")
      (node (ref "P3") (pin "42") (pinfunction "C10_42") (pintype "passive"))
      (node (ref "R41") (pin "1") (pinfunction "1_1") (pintype "passive"))
    )
    (net (code "66") (name "/MCU_BOOT0") (class "Default")
      (node (ref "P3") (pin "24") (pinfunction "B8_24") (pintype "passive"))
      (node (ref "R17") (pin "1") (pinfunction "1_1") (pintype "passive"))
    )
    (net (code "67") (name "/MCU_BOOT1") (class "Default")
      (node (ref "P3") (pin "25") (pinfunction "B9_25") (pintype "passive"))
      (node (ref "R18") (pin "1") (pinfunction "1_1") (pintype "passive"))
    )
    (net (code "68") (name "/MCU_I2C1_SCL") (class "Default")
      (node (ref "P3") (pin "27") (pinfunction "B11_27") (pintype "passive"))
      (node (ref "R22") (pin "1") (pinfunction "1_1") (pintype "passive"))
    )
    (net (code "69") (name "/MCU_I2C1_SDA") (class "Default")
      (node (ref "P3") (pin "26") (pinfunction "B10_26") (pintype "passive"))
      (node (ref "R20") (pin "1") (pinfunction "1_1") (pintype "passive"))
    )
    (net (code "70") (name "/MCU_I2C2_SCL") (class "Default")
      (node (ref "P3") (pin "29") (pinfunction "B13_29") (pintype "passive"))
      (node (ref "R24") (pin "1") (pinfunction "1_1") (pintype "passive"))
    )
    (net (code "71") (name "/MCU_I2C2_SDA") (class "Default")
      (node (ref "P3") (pin "28") (pinfunction "B12_28") (pintype "passive"))
      (node (ref "R23") (pin "1") (pinfunction "1_1") (pintype "passive"))
    )
    (net (code "72") (name "/MCU_RSTn") (class "Default")
      (node (ref "P3") (pin "23") (pinfunction "B7_23") (pintype "passive"))
      (node (ref "R16") (pin "1") (pinfunction "1_1") (pintype "passive"))
    )
    (net (code "73") (name "/OUT0") (class "Default")
      (node (ref "P2") (pin "44") (pinfunction "C12_44") (pintype "passive"))
      (node (ref "R40") (pin "2") (pinfunction "2_2") (pintype "passive"))
    )
    (net (code "74") (name "/PWR_BTN") (class "Default")
      (node (ref "R27") (pin "2") (pinfunction "2_2") (pintype "passive"))
    )
    (net (code "75") (name "/REG1_EN") (class "Default")
      (node (ref "R43") (pin "2") (pinfunction "2_2") (pintype "passive"))
    )
    (net (code "76") (name "/REG2_EN") (class "Default")
      (node (ref "R47") (pin "2") (pinfunction "2_2") (pintype "passive"))
    )
    (net (code "77") (name "/REG3_EN") (class "Default")
      (node (ref "R51") (pin "2") (pinfunction "2_2") (pintype "passive"))
    )
    (net (code "78") (name "/RS485_A") (class "Default")
      (node (ref "R45") (pin "1") (pinfunction "1_1") (pintype "passive"))
    )
    (net (code "79") (name "/RS485_B") (class "Default")
      (node (ref "R48") (pin "1") (pinfunction "1_1") (pintype "passive"))
    )
    (net (code "80") (name "/RX_N") (class "Default")
      (node (ref "P3") (pin "40") (pinfunction "C8_40") (pintype "passive"))
      (node (ref "R36") (pin "1") (pinfunction "1_1") (pintype "passive"))
    )
    (net (code "81") (name "/RX_P") (class "Default")
      (node (ref "P3") (pin "39") (pinfunction "C7_39") (pintype "passive"))
      (node (ref "R34") (pin "1") (pinfunction "1_1") (pintype "passive"))
    )
    (net (code "82") (name "/SOL2_N") (class "Default")
      (node (ref "P3") (pin "6") (pinfunction "A6_6") (pintype "passive"))
      (node (ref "R2") (pin "1") (pinfunction "1_1") (pintype "passive"))
    )
    (net (code "83") (name "/SOL2_P") (class "Default")
      (node (ref "P3") (pin "5") (pinfunction "A5_5") (pintype "passive"))
      (node (ref "R1") (pin "1") (pinfunction "1_1") (pintype "passive"))
    )
    (net (code "84") (name "/SOL3_N") (class "Default")
      (node (ref "P3") (pin "8") (pinfunction "A8_8") (pintype "passive"))
      (node (ref "R4") (pin "1") (pinfunction "1_1") (pintype "passive"))
    )
    (net (code "85") (name "/SOL3_P") (class "Default")
      (node (ref "P3") (pin "7") (pinfunction "A7_7") (pintype "passive"))
      (node (ref "R3") (pin "1") (pinfunction "1_1") (pintype "passive"))
    )
    (net (code "86") (name "/SOL4_N") (class "Default")
      (node (ref "P3") (pin "10") (pinfunction "A10_10") (pintype "passive"))
      (node (ref "R8") (pin "1") (pinfunction "1_1") (pintype "passive"))
    )
    (net (code "87") (name "/SOL4_P") (class "Default")
      (node (ref "P3") (pin "9") (pinfunction "A9_9") (pintype "passive"))
      (node (ref "R6") (pin "1") (pinfunction "1_1") (pintype "passive"))
    )
    (net (code "88") (name "/SOL5_N") (class "Default")
      (node (ref "P3") (pin "12") (pinfunction "A12_12") (pintype "passive"))
      (node (ref "R11") (pin "1") (pinfunction "1_1") (pintype "passive"))
    )
    (net (code "89") (name "/SOL5_P") (class "Default")
      (node (ref "P3") (pin "11") (pinfunction "A11_11") (pintype "passive"))
      (node (ref "R10") (pin "1") (pinfunction "1_1") (pintype "passive"))
    )
    (net (code "90") (name "/SOL6_N") (class "Default")
      (node (ref "P3") (pin "14") (pinfunction "A14_14") (pintype "passive"))
      (node (ref "R13") (pin "1") (pinfunction "1_1") (pintype "passive"))
    )
    (net (code "91") (name "/SOL6_P") (class "Default")
      (node (ref "P3") (pin "13") (pinfunction "A13_13") (pintype "passive"))
      (node (ref "R12") (pin "1") (pinfunction "1_1") (pintype "passive"))
    )
    (net (code "92") (name "/SOL7_N") (class "Default")
      (node (ref "P3") (pin "16") (pinfunction "A16_16") (pintype "passive"))
      (node (ref "R15") (pin "1") (pinfunction "1_1") (pintype "passive"))
    )
    (net (code "93") (name "/SOL7_P") (class "Default")
      (node (ref "P3") (pin "15") (pinfunction "A15_15") (pintype "passive"))
      (node (ref "R14") (pin "1") (pinfunction "1_1") (pintype "passive"))
    )
    (net (code "94") (name "/SOLENOID1_N") (class "Default")
      (node (ref "P6") (pin "4") (pinfunction "4_4") (pintype "passive"))
    )
    (net (code "95") (name "/SOLENOID1_P") (class "Default")
      (node (ref "P6") (pin "2") (pinfunction "2_2") (pintype "passive"))
    )
    (net (code "96") (name "/SOLENOID2_N") (class "Default")
      (node (ref "P6") (pin "8") (pinfunction "8_8") (pintype "passive"))
      (node (ref "R2") (pin "2") (pinfunction "2_2") (pintype "passive"))
    )
    (net (code "97") (name "/SOLENOID2_P") (class "Default")
      (node (ref "P6") (pin "6") (pinfunction "6_6") (pintype "passive"))
      (node (ref "R1") (pin "2") (pinfunction "2_2") (pintype "passive"))
    )
    (net (code "98") (name "/SOLENOID3_N") (class "Default")
      (node (ref "P6") (pin "12") (pinfunction "12_12") (pintype "passive"))
      (node (ref "R4") (pin "2") (pinfunction "2_2") (pintype "passive"))
    )
    (net (code "99") (name "/SOLENOID3_P") (class "Default")
      (node (ref "P6") (pin "10") (pinfunction "10_10") (pintype "passive"))
      (node (ref "R3") (pin "2") (pinfunction "2_2") (pintype "passive"))
    )
    (net (code "100") (name "/SPI2_MISOF") (class "Default")
      (node (ref "P4") (pin "27") (pinfunction "27_27") (pintype "passive"))
      (node (ref "R47") (pin "1") (pinfunction "1_1") (pintype "passive"))
    )
    (net (code "101") (name "/SPI2_MOSIF") (class "Default")
      (node (ref "P4") (pin "30") (pinfunction "30_30") (pintype "passive"))
      (node (ref "R51") (pin "1") (pinfunction "1_1") (pintype "passive"))
    )
    (net (code "102") (name "/SPI2_NSSF") (class "Default")
      (node (ref "P1") (pin "24") (pinfunction "24_24") (pintype "passive"))
      (node (ref "R43") (pin "1") (pinfunction "1_1") (pintype "passive"))
    )
    (net (code "103") (name "/SPI2_SCKF") (class "Default")
      (node (ref "P1") (pin "21") (pinfunction "21_21") (pintype "passive"))
      (node (ref "R39") (pin "1") (pinfunction "1_1") (pintype "passive"))
    )
    (net (code "104") (name "/SYS_PWR_BTN") (class "Default")
      (node (ref "P3") (pin "32") (pinfunction "B16_32") (pintype "passive"))
      (node (ref "R27") (pin "1") (pinfunction "1_1") (pintype "passive"))
    )
    (net (code "105") (name "/TIM1{slash}PWM3") (class "Default")
      (node (ref "P4") (pin "28") (pinfunction "28_28") (pintype "passive"))
      (node (ref "P5") (pin "25") (pinfunction "25_25") (pintype "passive"))
    )
    (net (code "106") (name "/TIM3{slash}PWM1") (class "Default")
      (node (ref "P1") (pin "15") (pinfunction "15_15") (pintype "passive"))
      (node (ref "R9") (pin "1") (pinfunction "1_1") (pintype "passive"))
    )
    (net (code "107") (name "/TIM4{slash}PWM2") (class "Default")
      (node (ref "P1") (pin "18") (pinfunction "18_18") (pintype "passive+no_connect"))
    )
    (net (code "108") (name "/TIM9{slash}PWM0") (class "Default")
      (node (ref "P4") (pin "25") (pinfunction "25_25") (pintype "passive"))
      (node (ref "P5") (pin "15") (pinfunction "15_15") (pintype "passive"))
    )
    (net (code "109") (name "/TX_N") (class "Default")
      (node (ref "P3") (pin "38") (pinfunction "C6_38") (pintype "passive"))
      (node (ref "R32") (pin "1") (pinfunction "1_1") (pintype "passive"))
    )
    (net (code "110") (name "/TX_P") (class "Default")
      (node (ref "P3") (pin "37") (pinfunction "C5_37") (pintype "passive"))
      (node (ref "R30") (pin "1") (pinfunction "1_1") (pintype "passive"))
    )
    (net (code "111") (name "/UART4_RXF") (class "Default")
      (node (ref "P4") (pin "9") (pinfunction "9_9") (pintype "passive"))
      (node (ref "R52") (pin "2") (pinfunction "2_2") (pintype "passive"))
    )
    (net (code "112") (name "/UART4_TXF") (class "Default")
      (node (ref "P4") (pin "12") (pinfunction "12_12") (pintype "passive"))
      (node (ref "R50") (pin "2") (pinfunction "2_2") (pintype "passive"))
    )
    (net (code "113") (name "/UART7_RXF") (class "Default")
      (node (ref "P1") (pin "36") (pinfunction "36_36") (pintype "passive"))
      (node (ref "R29") (pin "1") (pinfunction "1_1") (pintype "passive"))
      (node (ref "R38") (pin "2") (pinfunction "2_2") (pintype "passive"))
    )
    (net (code "114") (name "/UART7_TXF") (class "Default")
      (node (ref "P1") (pin "33") (pinfunction "33_33") (pintype "passive"))
      (node (ref "R25") (pin "2") (pinfunction "2_2") (pintype "passive"))
    )
    (net (code "115") (name "/USART1_RXF_BL") (class "Default")
      (node (ref "P4") (pin "11") (pinfunction "11_11") (pintype "passive"))
    )
    (net (code "116") (name "/USART1_TXF_BL") (class "Default")
      (node (ref "P4") (pin "14") (pinfunction "14_14") (pintype "passive"))
    )
    (net (code "117") (name "/USART2_CTSF") (class "Default")
      (node (ref "P4") (pin "3") (pinfunction "3_3") (pintype "passive"))
      (node (ref "P6") (pin "1") (pinfunction "1_1") (pintype "passive"))
    )
    (net (code "118") (name "/USART2_RTSF") (class "Default")
      (node (ref "P4") (pin "6") (pinfunction "6_6") (pintype "passive"))
      (node (ref "P6") (pin "5") (pinfunction "5_5") (pintype "passive"))
    )
    (net (code "119") (name "/USART2_RXF") (class "Default")
      (node (ref "P4") (pin "8") (pinfunction "8_8") (pintype "passive"))
      (node (ref "P6") (pin "7") (pinfunction "7_7") (pintype "passive"))
    )
    (net (code "120") (name "/USART2_TXF") (class "Default")
      (node (ref "P4") (pin "5") (pinfunction "5_5") (pintype "passive"))
      (node (ref "P6") (pin "3") (pinfunction "3_3") (pintype "passive"))
    )
    (net (code "121") (name "/USART3_CTSF") (class "Default")
      (node (ref "P1") (pin "17") (pinfunction "17_17") (pintype "passive"))
    )
    (net (code "122") (name "/USART3_RTSF") (class "Default")
      (node (ref "P1") (pin "22") (pinfunction "22_22") (pintype "passive"))
    )
    (net (code "123") (name "/USART3_RXF") (class "Default")
      (node (ref "P1") (pin "20") (pinfunction "20_20") (pintype "passive"))
    )
    (net (code "124") (name "/USART3_TXF") (class "Default")
      (node (ref "P1") (pin "19") (pinfunction "19_19") (pintype "passive"))
    )
    (net (code "125") (name "/USB0_D_N") (class "Default")
      (node (ref "R46") (pin "2") (pinfunction "2_2") (pintype "passive"))
    )
    (net (code "126") (name "/USB0_D_P") (class "Default")
      (node (ref "R44") (pin "2") (pinfunction "2_2") (pintype "passive"))
    )
    (net (code "127") (name "/USB_D_N") (class "Default")
      (node (ref "P1") (pin "11") (pinfunction "11_11") (pintype "passive"))
    )
    (net (code "128") (name "/USB_D_P") (class "Default")
      (node (ref "P1") (pin "12") (pinfunction "12_12") (pintype "passive"))
    )
    (net (code "129") (name "/USB_N") (class "Default")
      (node (ref "P3") (pin "45") (pinfunction "C13_45") (pintype "passive"))
      (node (ref "R46") (pin "1") (pinfunction "1_1") (pintype "passive"))
    )
    (net (code "130") (name "/USB_P") (class "Default")
      (node (ref "P3") (pin "44") (pinfunction "C12_44") (pintype "passive"))
      (node (ref "R44") (pin "1") (pinfunction "1_1") (pintype "passive"))
    )
    (net (code "131") (name "/USB_VBUS") (class "Default")
      (node (ref "P1") (pin "14") (pinfunction "14_14") (pintype "passive"))
    )
    (net (code "132") (name "/VSO1A_N") (class "Default")
      (node (ref "P6") (pin "16") (pinfunction "16_16") (pintype "passive"))
      (node (ref "R8") (pin "2") (pinfunction "2_2") (pintype "passive"))
    )
    (net (code "133") (name "/VSO1A_P") (class "Default")
      (node (ref "P6") (pin "14") (pinfunction "14_14") (pintype "passive"))
      (node (ref "R6") (pin "2") (pinfunction "2_2") (pintype "passive"))
    )
    (net (code "134") (name "/VSO1B_N") (class "Default")
      (node (ref "P6") (pin "24") (pinfunction "24_24") (pintype "passive"))
      (node (ref "R13") (pin "2") (pinfunction "2_2") (pintype "passive"))
    )
    (net (code "135") (name "/VSO1B_P") (class "Default")
      (node (ref "P6") (pin "22") (pinfunction "22_22") (pintype "passive"))
      (node (ref "R12") (pin "2") (pinfunction "2_2") (pintype "passive"))
    )
    (net (code "136") (name "/VSO2A_N") (class "Default")
      (node (ref "P6") (pin "20") (pinfunction "20_20") (pintype "passive"))
      (node (ref "R11") (pin "2") (pinfunction "2_2") (pintype "passive"))
    )
    (net (code "137") (name "/VSO2A_P") (class "Default")
      (node (ref "P6") (pin "18") (pinfunction "18_18") (pintype "passive"))
      (node (ref "R10") (pin "2") (pinfunction "2_2") (pintype "passive"))
    )
    (net (code "138") (name "/VSO2B_N") (class "Default")
      (node (ref "P6") (pin "28") (pinfunction "28_28") (pintype "passive"))
      (node (ref "R15") (pin "2") (pinfunction "2_2") (pintype "passive"))
    )
    (net (code "139") (name "/VSO2B_P") (class "Default")
      (node (ref "P6") (pin "26") (pinfunction "26_26") (pintype "passive"))
      (node (ref "R14") (pin "2") (pinfunction "2_2") (pintype "passive"))
    )
    (net (code "140") (name "/nRESETF") (class "Default")
      (node (ref "P1") (pin "4") (pinfunction "4_4") (pintype "passive"))
      (node (ref "R16") (pin "2") (pinfunction "2_2") (pintype "passive"))
    )
    (net (code "141") (name "12V0A") (class "Default")
      (node (ref "P6") (pin "11") (pinfunction "11_11") (pintype "passive"))
      (node (ref "R53") (pin "1") (pinfunction "1_1") (pintype "passive"))
    )
    (net (code "142") (name "12V0B") (class "Default")
      (node (ref "P6") (pin "15") (pinfunction "15_15") (pintype "passive"))
      (node (ref "R54") (pin "1") (pinfunction "1_1") (pintype "passive"))
    )
    (net (code "143") (name "12V0C") (class "Default")
      (node (ref "P6") (pin "19") (pinfunction "19_19") (pintype "passive"))
      (node (ref "R55") (pin "1") (pinfunction "1_1") (pintype "passive"))
    )
    (net (code "144") (name "12V0D") (class "Default")
      (node (ref "P6") (pin "23") (pinfunction "23_23") (pintype "passive"))
      (node (ref "R56") (pin "1") (pinfunction "1_1") (pintype "passive"))
    )
    (net (code "145") (name "12V0E") (class "Default")
      (node (ref "P6") (pin "27") (pinfunction "27_27") (pintype "passive"))
      (node (ref "R57") (pin "1") (pinfunction "1_1") (pintype "passive"))
    )
    (net (code "146") (name "18_24VDC") (class "Default")
      (node (ref "P2") (pin "19") (pinfunction "B3_19") (pintype "passive"))
      (node (ref "P2") (pin "20") (pinfunction "B4_20") (pintype "passive"))
      (node (ref "P2") (pin "21") (pinfunction "B5_21") (pintype "passive"))
      (node (ref "P2") (pin "3") (pinfunction "A3_3") (pintype "passive"))
      (node (ref "P2") (pin "35") (pinfunction "C3_35") (pintype "passive"))
      (node (ref "P2") (pin "36") (pinfunction "C4_36") (pintype "passive"))
      (node (ref "P2") (pin "37") (pinfunction "C5_37") (pintype "passive"))
      (node (ref "P2") (pin "4") (pinfunction "A4_4") (pintype "passive"))
      (node (ref "P2") (pin "5") (pinfunction "A5_5") (pintype "passive"))
      (node (ref "P3") (pin "18") (pinfunction "B2_18") (pintype "passive"))
      (node (ref "P3") (pin "19") (pinfunction "B3_19") (pintype "passive"))
      (node (ref "P3") (pin "2") (pinfunction "A2_2") (pintype "passive"))
      (node (ref "P3") (pin "3") (pinfunction "A3_3") (pintype "passive"))
      (node (ref "P3") (pin "34") (pinfunction "C2_34") (pintype "passive"))
      (node (ref "P3") (pin "35") (pinfunction "C3_35") (pintype "passive"))
    )
    (net (code "147") (name "GND") (class "Default")
      (node (ref "P1") (pin "1") (pinfunction "1_1") (pintype "passive"))
      (node (ref "P1") (pin "39") (pinfunction "39_39") (pintype "passive"))
      (node (ref "P2") (pin "1") (pinfunction "A1_1") (pintype "passive"))
      (node (ref "P2") (pin "17") (pinfunction "B1_17") (pintype "passive"))
      (node (ref "P2") (pin "18") (pinfunction "B2_18") (pintype "passive"))
      (node (ref "P2") (pin "2") (pinfunction "A2_2") (pintype "passive"))
      (node (ref "P2") (pin "22") (pinfunction "B6_22") (pintype "passive"))
      (node (ref "P2") (pin "23") (pinfunction "B7_23") (pintype "passive"))
      (node (ref "P2") (pin "33") (pinfunction "C1_33") (pintype "passive"))
      (node (ref "P2") (pin "34") (pinfunction "C2_34") (pintype "passive"))
      (node (ref "P2") (pin "38") (pinfunction "C6_38") (pintype "passive"))
      (node (ref "P2") (pin "39") (pinfunction "C7_39") (pintype "passive"))
      (node (ref "P2") (pin "6") (pinfunction "A6_6") (pintype "passive"))
      (node (ref "P2") (pin "7") (pinfunction "A7_7") (pintype "passive"))
      (node (ref "P3") (pin "1") (pinfunction "A1_1") (pintype "passive"))
      (node (ref "P3") (pin "17") (pinfunction "B1_17") (pintype "passive"))
      (node (ref "P3") (pin "20") (pinfunction "B4_20") (pintype "passive"))
      (node (ref "P3") (pin "33") (pinfunction "C1_33") (pintype "passive"))
      (node (ref "P3") (pin "36") (pinfunction "C4_36") (pintype "passive"))
      (node (ref "P3") (pin "4") (pinfunction "A4_4") (pintype "passive"))
      (node (ref "P4") (pin "1") (pinfunction "1_1") (pintype "passive"))
      (node (ref "P4") (pin "2") (pinfunction "2_2") (pintype "passive"))
      (node (ref "P4") (pin "38") (pinfunction "38_38") (pintype "passive"))
      (node (ref "P4") (pin "39") (pinfunction "39_39") (pintype "passive"))
      (node (ref "P4") (pin "4") (pinfunction "4_4") (pintype "passive"))
      (node (ref "P4") (pin "40") (pinfunction "40_40") (pintype "passive"))
      (node (ref "P5") (pin "1") (pinfunction "1_1") (pintype "passive"))
      (node (ref "P5") (pin "10") (pinfunction "10_10") (pintype "passive"))
      (node (ref "P5") (pin "2") (pinfunction "2_2") (pintype "passive"))
      (node (ref "P5") (pin "20") (pinfunction "20_20") (pintype "passive"))
      (node (ref "P5") (pin "29") (pinfunction "29_29") (pintype "passive"))
      (node (ref "P5") (pin "30") (pinfunction "30_30") (pintype "passive"))
      (node (ref "P6") (pin "13") (pinfunction "13_13") (pintype "passive"))
      (node (ref "P6") (pin "17") (pinfunction "17_17") (pintype "passive"))
      (node (ref "P6") (pin "21") (pinfunction "21_21") (pintype "passive"))
      (node (ref "P6") (pin "25") (pinfunction "25_25") (pintype "passive"))
      (node (ref "P6") (pin "29") (pinfunction "29_29") (pintype "passive"))
      (node (ref "P6") (pin "30") (pinfunction "30_30") (pintype "passive"))
    )
    (net (code "148") (name "Net-(P2C-C15)") (class "Default")
      (node (ref "P2") (pin "47") (pinfunction "C15_47") (pintype "passive"))
      (node (ref "R45") (pin "2") (pinfunction "2_2") (pintype "passive"))
    )
    (net (code "149") (name "Net-(P2C-C16)") (class "Default")
      (node (ref "P2") (pin "48") (pinfunction "C16_48") (pintype "passive"))
      (node (ref "R48") (pin "2") (pinfunction "2_2") (pintype "passive"))
    )
    (net (code "150") (name "Net-(P3C-C11)") (class "Default")
      (node (ref "P3") (pin "43") (pinfunction "C11_43") (pintype "passive"))
      (node (ref "R42") (pin "1") (pinfunction "1_1") (pintype "passive"))
    )
    (net (code "151") (name "Net-(P3C-C14)") (class "Default")
      (node (ref "P3") (pin "46") (pinfunction "C14_46") (pintype "passive"))
      (node (ref "R49") (pin "1") (pinfunction "1_1") (pintype "passive"))
    )
    (net (code "152") (name "USB_VIN1") (class "Default")
      (node (ref "R49") (pin "2") (pinfunction "2_2") (pintype "passive"))
    )
    (net (code "153") (name "VDD_3V3") (class "Default")
      (node (ref "P1") (pin "2") (pinfunction "2_2") (pintype "passive"))
      (node (ref "P2") (pin "8") (pinfunction "A8_8") (pintype "passive"))
      (node (ref "P5") (pin "18") (pinfunction "18_18") (pintype "passive"))
      (node (ref "R28") (pin "2") (pinfunction "2_2") (pintype "passive"))
      (node (ref "R29") (pin "2") (pinfunction "2_2") (pintype "passive"))
    )
    (net (code "154") (name "VDD_5V0") (class "Default")
      (node (ref "P3") (pin "22") (pinfunction "B6_22") (pintype "passive"))
      (node (ref "P5") (pin "22") (pinfunction "22_22") (pintype "passive"))
    )
    (net (code "155") (name "VDD_12V0") (class "Default")
      (node (ref "P3") (pin "21") (pinfunction "B5_21") (pintype "passive"))
      (node (ref "R53") (pin "2") (pinfunction "2_2") (pintype "passive"))
      (node (ref "R54") (pin "2") (pinfunction "2_2") (pintype "passive"))
      (node (ref "R55") (pin "2") (pinfunction "2_2") (pintype "passive"))
      (node (ref "R56") (pin "2") (pinfunction "2_2") (pintype "passive"))
      (node (ref "R57") (pin "2") (pinfunction "2_2") (pintype "passive"))
    )
    (net (code "156") (name "V_FLOW2") (class "Default")
      (node (ref "R42") (pin "2") (pinfunction "2_2") (pintype "passive"))
    )
    (net (code "157") (name "unconnected-(P2A-A12-Pad12)") (class "Default")
      (node (ref "P2") (pin "12") (pinfunction "A12_12") (pintype "passive+no_connect"))
    )
    (net (code "158") (name "unconnected-(P2A-A13-Pad13)") (class "Default")
      (node (ref "P2") (pin "13") (pinfunction "A13_13") (pintype "passive+no_connect"))
    )
    (net (code "159") (name "unconnected-(P2A-A14-Pad14)") (class "Default")
      (node (ref "P2") (pin "14") (pinfunction "A14_14") (pintype "passive+no_connect"))
    )
    (net (code "160") (name "unconnected-(P2A-A15-Pad15)") (class "Default")
      (node (ref "P2") (pin "15") (pinfunction "A15_15") (pintype "passive+no_connect"))
    )
    (net (code "161") (name "unconnected-(P2A-A16-Pad16)") (class "Default")
      (node (ref "P2") (pin "16") (pinfunction "A16_16") (pintype "passive+no_connect"))
    )
    (net (code "162") (name "unconnected-(P2B-B8-Pad24)") (class "Default")
      (node (ref "P2") (pin "24") (pinfunction "B8_24") (pintype "passive+no_connect"))
    )
    (net (code "163") (name "unconnected-(P2B-B9-Pad25)") (class "Default")
      (node (ref "P2") (pin "25") (pinfunction "B9_25") (pintype "passive+no_connect"))
    )
    (net (code "164") (name "unconnected-(P2B-B10-Pad26)") (class "Default")
      (node (ref "P2") (pin "26") (pinfunction "B10_26") (pintype "passive+no_connect"))
    )
    (net (code "165") (name "unconnected-(P2B-B13-Pad29)") (class "Default")
      (node (ref "P2") (pin "29") (pinfunction "B13_29") (pintype "passive+no_connect"))
    )
    (net (code "166") (name "unconnected-(P2B-B14-Pad30)") (class "Default")
      (node (ref "P2") (pin "30") (pinfunction "B14_30") (pintype "passive+no_connect"))
    )
    (net (code "167") (name "unconnected-(P2B-B15-Pad31)") (class "Default")
      (node (ref "P2") (pin "31") (pinfunction "B15_31") (pintype "passive+no_connect"))
    )
    (net (code "168") (name "unconnected-(P2B-B16-Pad32)") (class "Default")
      (node (ref "P2") (pin "32") (pinfunction "B16_32") (pintype "passive+no_connect"))
    )
    (net (code "169") (name "unconnected-(P2C-C13-Pad45)") (class "Default")
      (node (ref "P2") (pin "45") (pinfunction "C13_45") (pintype "passive+no_connect"))
    )
    (net (code "170") (name "unconnected-(P2C-C14-Pad46)") (class "Default")
      (node (ref "P2") (pin "46") (pinfunction "C14_46") (pintype "passive+no_connect"))
    )
  )
)
